# Orientation_bracelet.net
KiCad netlist of a schematic drawn in EAGLE
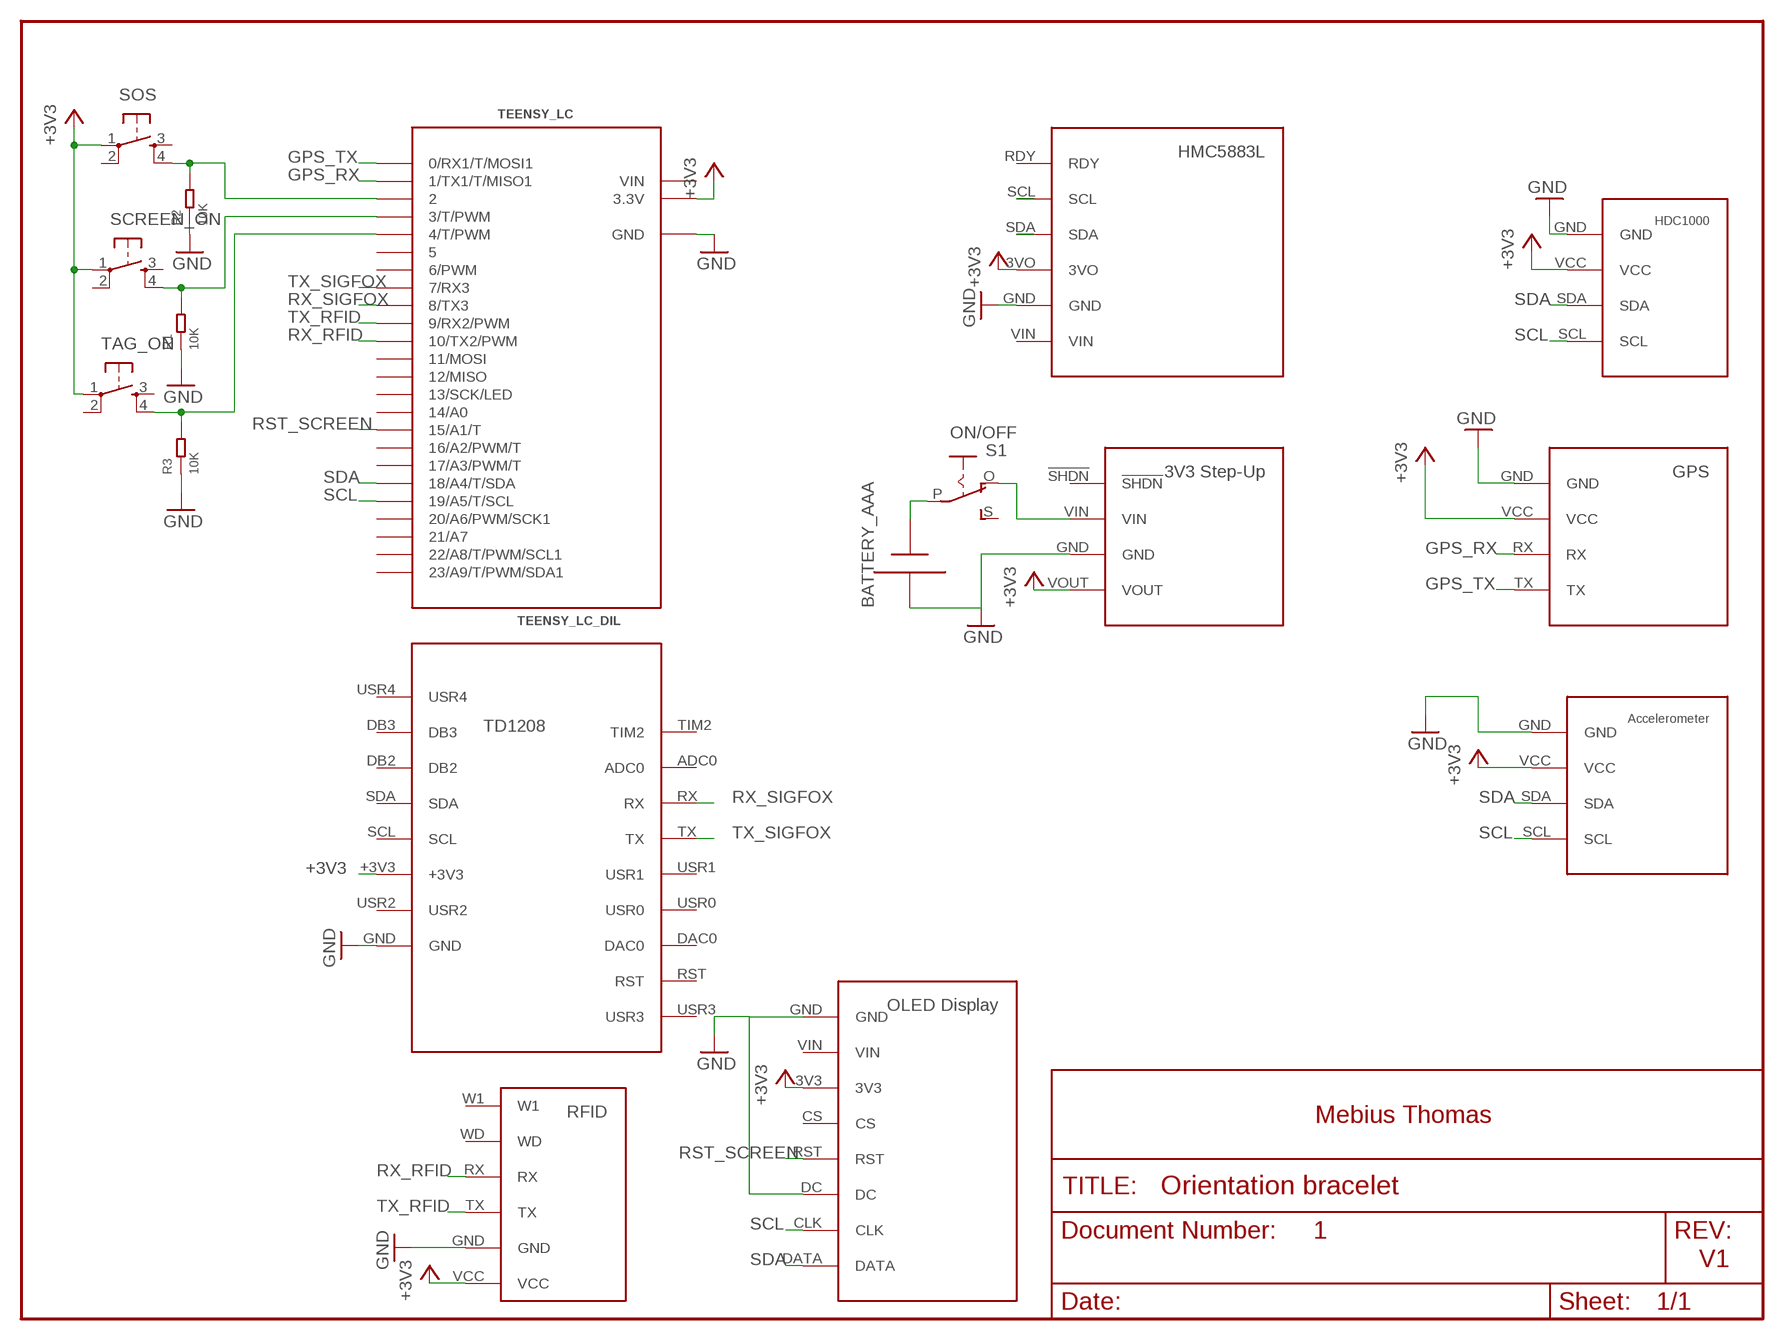
[diagram p0: schematic, sheet 1]

(export (version "E")
  (design (tool "Eeschema 10.0.6"))
  (components
    (comp (ref "BATTERY_AAA")
      (value "AAA")
      (footprint "eagle-import:12BH412")
      (libsource (lib "eagle-import") (part "AAA"))
    )
    (comp (ref "ON/OFF")
      (value "S1")
      (footprint "eagle-import:EG1218")
      (libsource (lib "eagle-import") (part "EG1218S"))
    )
    (comp (ref "R1")
      (value "10K")
      (footprint "eagle-import:PR-D2.3XL6.5MM")
      (fields (field (name "MPN") "FHCFR-1/4W-223J"))
      (libsource (lib "eagle-import") (part "DIP-RES-22K-5%-1/4W(PR-D2.3XL6.5MM)"))
    )
    (comp (ref "R2")
      (value "10K")
      (footprint "eagle-import:PR-D2.3XL6.5MM")
      (fields (field (name "MPN") "FHCFR-1/4W-223J"))
      (libsource (lib "eagle-import") (part "DIP-RES-22K-5%-1/4W(PR-D2.3XL6.5MM)"))
    )
    (comp (ref "R3")
      (value "10K")
      (footprint "eagle-import:PR-D2.3XL6.5MM")
      (fields (field (name "MPN") "FHCFR-1/4W-223J"))
      (libsource (lib "eagle-import") (part "DIP-RES-22K-5%-1/4W(PR-D2.3XL6.5MM)"))
    )
    (comp (ref "SCREEN_ON")
      (value "TAC_SWITCHPTH")
      (footprint "eagle-import:TACTILE-PTH")
      (libsource (lib "eagle-import") (part "TAC_SWITCHPTH"))
    )
    (comp (ref "SOS")
      (value "TAC_SWITCHPTH")
      (footprint "eagle-import:TACTILE-PTH")
      (libsource (lib "eagle-import") (part "TAC_SWITCHPTH"))
    )
    (comp (ref "TAG_ON")
      (value "TAC_SWITCHPTH")
      (footprint "eagle-import:TACTILE-PTH")
      (libsource (lib "eagle-import") (part "TAC_SWITCHPTH"))
    )
    (comp (ref "TEENSY_LC")
      (value "TEENSY_LC_DIL")
      (footprint "eagle-import:TEENSY_3.0-3.2&LC_DIL")
      (libsource (lib "eagle-import") (part "TEENSY_LC_DIL"))
    )
    (comp (ref "U$1")
      (value "OLED_DISPLAY")
      (footprint "eagle-import:OLED_DISPLAY")
      (libsource (lib "eagle-import") (part "OLED_DISPLAY"))
    )
    (comp (ref "U$2")
      (value "RFID\"")
      (footprint "eagle-import:RFID")
      (libsource (lib "eagle-import") (part "RFID{dblquote}"))
    )
    (comp (ref "U$3")
      (value "3V3_STEP-UP")
      (footprint "eagle-import:3V3_STEP-UP")
      (libsource (lib "eagle-import") (part "3V3_STEP-UP"))
    )
    (comp (ref "U$4")
      (value "ACCELEROMETER")
      (footprint "eagle-import:ACCELEROMETER")
      (libsource (lib "eagle-import") (part "ACCELEROMETER"))
    )
    (comp (ref "U$5")
      (value "HDC1000")
      (footprint "eagle-import:HDC1000")
      (libsource (lib "eagle-import") (part "HDC1000"))
    )
    (comp (ref "U$6")
      (value "GPS")
      (footprint "eagle-import:GPS")
      (libsource (lib "eagle-import") (part "GPS"))
    )
    (comp (ref "U$7")
      (value "HMC5883L")
      (footprint "eagle-import:HMC5883L")
      (libsource (lib "eagle-import") (part "HMC5883L"))
    )
    (comp (ref "U$8")
      (value "TD1208")
      (footprint "eagle-import:TD1208")
      (libsource (lib "eagle-import") (part "TD1208"))
    )
  )
  (nets
    (net (code "1") (name "+3V3") (class "Default")
      (node (ref "SCREEN_ON") (pin "1") (pinfunction "1_1") (pintype "passive"))
      (node (ref "SOS") (pin "1") (pinfunction "1_1") (pintype "passive"))
      (node (ref "TAG_ON") (pin "1") (pinfunction "1_1") (pintype "passive"))
      (node (ref "TEENSY_LC") (pin "3.3V") (pinfunction "3.3V_3.3V") (pintype "power_in"))
      (node (ref "U$1") (pin "3V3") (pinfunction "3V3_3V3") (pintype "bidirectional"))
      (node (ref "U$2") (pin "VCC") (pinfunction "VCC_VCC") (pintype "bidirectional"))
      (node (ref "U$3") (pin "VOUT") (pinfunction "VOUT_VOUT") (pintype "bidirectional"))
      (node (ref "U$4") (pin "VCC") (pinfunction "VCC_VCC") (pintype "bidirectional"))
      (node (ref "U$5") (pin "VCC") (pinfunction "VCC_VCC") (pintype "bidirectional"))
      (node (ref "U$6") (pin "VCC") (pinfunction "VCC_VCC") (pintype "bidirectional"))
      (node (ref "U$7") (pin "3VO") (pinfunction "3VO_3VO") (pintype "bidirectional"))
      (node (ref "U$8") (pin "+3V3") (pinfunction "+3V3_+3V3") (pintype "bidirectional"))
    )
    (net (code "2") (name "/GPS_RX") (class "Default")
      (node (ref "TEENSY_LC") (pin "1") (pinfunction "1/TX1/T/MISO1_1") (pintype "bidirectional"))
      (node (ref "U$6") (pin "RX") (pinfunction "RX_RX") (pintype "bidirectional"))
    )
    (net (code "3") (name "/GPS_TX") (class "Default")
      (node (ref "TEENSY_LC") (pin "0") (pinfunction "0/RX1/T/MOSI1_0") (pintype "bidirectional"))
      (node (ref "U$6") (pin "TX") (pinfunction "TX_TX") (pintype "bidirectional"))
    )
    (net (code "4") (name "/RST_SCREEN") (class "Default")
      (node (ref "TEENSY_LC") (pin "15/A1") (pinfunction "15/A1/T_15/A1") (pintype "bidirectional"))
      (node (ref "U$1") (pin "RST") (pinfunction "RST_RST") (pintype "bidirectional"))
    )
    (net (code "5") (name "/RX_RFID") (class "Default")
      (node (ref "TEENSY_LC") (pin "10") (pinfunction "10/TX2/PWM_10") (pintype "bidirectional"))
      (node (ref "U$2") (pin "RX") (pinfunction "RX_RX") (pintype "bidirectional"))
    )
    (net (code "6") (name "/RX_SIGFOX") (class "Default")
      (node (ref "TEENSY_LC") (pin "8") (pinfunction "8/TX3_8") (pintype "bidirectional"))
      (node (ref "U$8") (pin "RX") (pinfunction "RX_RX") (pintype "bidirectional"))
    )
    (net (code "7") (name "/SCL") (class "Default")
      (node (ref "TEENSY_LC") (pin "19/A5") (pinfunction "19/A5/T/SCL_19/A5") (pintype "bidirectional"))
      (node (ref "U$1") (pin "CLK") (pinfunction "CLK_CLK") (pintype "bidirectional"))
      (node (ref "U$4") (pin "SCL") (pinfunction "SCL_SCL") (pintype "bidirectional"))
      (node (ref "U$5") (pin "SCL") (pinfunction "SCL_SCL") (pintype "bidirectional"))
      (node (ref "U$7") (pin "SCL") (pinfunction "SCL_SCL") (pintype "bidirectional"))
    )
    (net (code "8") (name "/SDA") (class "Default")
      (node (ref "TEENSY_LC") (pin "18/A4") (pinfunction "18/A4/T/SDA_18/A4") (pintype "bidirectional"))
      (node (ref "U$1") (pin "DATA") (pinfunction "DATA_DATA") (pintype "bidirectional"))
      (node (ref "U$4") (pin "SDA") (pinfunction "SDA_SDA") (pintype "bidirectional"))
      (node (ref "U$5") (pin "SDA") (pinfunction "SDA_SDA") (pintype "bidirectional"))
      (node (ref "U$7") (pin "SDA") (pinfunction "SDA_SDA") (pintype "bidirectional"))
    )
    (net (code "9") (name "/TX_RFID") (class "Default")
      (node (ref "TEENSY_LC") (pin "9") (pinfunction "9/RX2/PWM_9") (pintype "bidirectional"))
      (node (ref "U$2") (pin "TX") (pinfunction "TX_TX") (pintype "bidirectional"))
    )
    (net (code "10") (name "/TX_SIGFOX") (class "Default")
      (node (ref "TEENSY_LC") (pin "7") (pinfunction "7/RX3_7") (pintype "bidirectional"))
      (node (ref "U$8") (pin "TX") (pinfunction "TX_TX") (pintype "bidirectional"))
    )
    (net (code "11") (name "/VIN") (class "Default")
      (node (ref "TEENSY_LC") (pin "VIN") (pinfunction "VIN_VIN") (pintype "power_in"))
    )
    (net (code "12") (name "GND") (class "Default")
      (node (ref "BATTERY_AAA") (pin "-") (pinfunction "-_-") (pintype "bidirectional"))
      (node (ref "R1") (pin "1") (pinfunction "1_1") (pintype "passive"))
      (node (ref "R2") (pin "1") (pinfunction "1_1") (pintype "passive"))
      (node (ref "R3") (pin "1") (pinfunction "1_1") (pintype "passive"))
      (node (ref "TEENSY_LC") (pin "AGND") (pinfunction "GND_AGND") (pintype "power_in"))
      (node (ref "TEENSY_LC") (pin "GND") (pinfunction "GND_GND") (pintype "power_in"))
      (node (ref "U$1") (pin "DC") (pinfunction "DC_DC") (pintype "bidirectional"))
      (node (ref "U$1") (pin "GND") (pinfunction "GND_GND") (pintype "bidirectional"))
      (node (ref "U$2") (pin "GND") (pinfunction "GND_GND") (pintype "bidirectional"))
      (node (ref "U$3") (pin "GND") (pinfunction "GND_GND") (pintype "bidirectional"))
      (node (ref "U$4") (pin "GND") (pinfunction "GND_GND") (pintype "bidirectional"))
      (node (ref "U$5") (pin "GND") (pinfunction "GND_GND") (pintype "bidirectional"))
      (node (ref "U$6") (pin "GND") (pinfunction "GND_GND") (pintype "bidirectional"))
      (node (ref "U$7") (pin "GND") (pinfunction "GND_GND") (pintype "bidirectional"))
      (node (ref "U$8") (pin "GND") (pinfunction "GND_GND") (pintype "bidirectional"))
    )
    (net (code "13") (name "Net-(BATTERY_AAA-Pad+)") (class "Default")
      (node (ref "BATTERY_AAA") (pin "+") (pinfunction "+_+") (pintype "bidirectional"))
      (node (ref "ON/OFF") (pin "P") (pinfunction "P_P") (pintype "passive"))
    )
    (net (code "14") (name "Net-(ON/OFF-PadO)") (class "Default")
      (node (ref "ON/OFF") (pin "O") (pinfunction "O_O") (pintype "passive"))
      (node (ref "U$3") (pin "VIN") (pinfunction "VIN_VIN") (pintype "bidirectional"))
    )
    (net (code "15") (name "Net-(R2-Pad2)") (class "Default")
      (node (ref "R2") (pin "2") (pinfunction "2_2") (pintype "passive"))
      (node (ref "SOS") (pin "4") (pinfunction "4_4") (pintype "passive"))
      (node (ref "TEENSY_LC") (pin "2") (pinfunction "2_2") (pintype "bidirectional"))
    )
    (net (code "16") (name "Net-(TEENSY_LC-3{slash}T{slash}PWM)") (class "Default")
      (node (ref "R1") (pin "2") (pinfunction "2_2") (pintype "passive"))
      (node (ref "SCREEN_ON") (pin "4") (pinfunction "4_4") (pintype "passive"))
      (node (ref "TEENSY_LC") (pin "3") (pinfunction "3/T/PWM_3") (pintype "bidirectional"))
    )
    (net (code "17") (name "Net-(TEENSY_LC-4{slash}T{slash}PWM)") (class "Default")
      (node (ref "R3") (pin "2") (pinfunction "2_2") (pintype "passive"))
      (node (ref "TAG_ON") (pin "4") (pinfunction "4_4") (pintype "passive"))
      (node (ref "TEENSY_LC") (pin "4") (pinfunction "4/T/PWM_4") (pintype "bidirectional"))
    )
    (net (code "18") (name "unconnected-(ON/OFF-PadS)") (class "Default")
      (node (ref "ON/OFF") (pin "S") (pinfunction "S_S") (pintype "passive"))
    )
    (net (code "19") (name "unconnected-(SCREEN_ON-Pad2)") (class "Default")
      (node (ref "SCREEN_ON") (pin "2") (pinfunction "2_2") (pintype "passive"))
    )
    (net (code "20") (name "unconnected-(SCREEN_ON-Pad3)") (class "Default")
      (node (ref "SCREEN_ON") (pin "3") (pinfunction "3_3") (pintype "passive"))
    )
    (net (code "21") (name "unconnected-(SOS-Pad2)") (class "Default")
      (node (ref "SOS") (pin "2") (pinfunction "2_2") (pintype "passive"))
    )
    (net (code "22") (name "unconnected-(SOS-Pad3)") (class "Default")
      (node (ref "SOS") (pin "3") (pinfunction "3_3") (pintype "passive"))
    )
    (net (code "23") (name "unconnected-(TAG_ON-Pad2)") (class "Default")
      (node (ref "TAG_ON") (pin "2") (pinfunction "2_2") (pintype "passive"))
    )
    (net (code "24") (name "unconnected-(TAG_ON-Pad3)") (class "Default")
      (node (ref "TAG_ON") (pin "3") (pinfunction "3_3") (pintype "passive"))
    )
    (net (code "25") (name "unconnected-(TEENSY_LC-6{slash}PWM-Pad6)") (class "Default")
      (node (ref "TEENSY_LC") (pin "6") (pinfunction "6/PWM_6") (pintype "bidirectional"))
    )
    (net (code "26") (name "unconnected-(TEENSY_LC-11{slash}MOSI-Pad11)") (class "Default")
      (node (ref "TEENSY_LC") (pin "11") (pinfunction "11/MOSI_11") (pintype "bidirectional"))
    )
    (net (code "27") (name "unconnected-(TEENSY_LC-12{slash}MISO-Pad12)") (class "Default")
      (node (ref "TEENSY_LC") (pin "12") (pinfunction "12/MISO_12") (pintype "bidirectional"))
    )
    (net (code "28") (name "unconnected-(TEENSY_LC-13{slash}SCK{slash}LED-Pad13)") (class "Default")
      (node (ref "TEENSY_LC") (pin "13") (pinfunction "13/SCK/LED_13") (pintype "bidirectional"))
    )
    (net (code "29") (name "unconnected-(TEENSY_LC-16{slash}A2{slash}PWM{slash}T-Pad16{slash}A2)") (class "Default")
      (node (ref "TEENSY_LC") (pin "16/A2") (pinfunction "16/A2/PWM/T_16/A2") (pintype "bidirectional"))
    )
    (net (code "30") (name "unconnected-(TEENSY_LC-17{slash}A3{slash}PWM{slash}T-Pad17{slash}A3)") (class "Default")
      (node (ref "TEENSY_LC") (pin "17/A3") (pinfunction "17/A3/PWM/T_17/A3") (pintype "bidirectional"))
    )
    (net (code "31") (name "unconnected-(TEENSY_LC-20{slash}A6{slash}PWM{slash}SCK1-Pad20{slash}A6)") (class "Default")
      (node (ref "TEENSY_LC") (pin "20/A6") (pinfunction "20/A6/PWM/SCK1_20/A6") (pintype "bidirectional"))
    )
    (net (code "32") (name "unconnected-(TEENSY_LC-22{slash}A8{slash}T{slash}PWM{slash}SCL1-Pad22{slash}A8)") (class "Default")
      (node (ref "TEENSY_LC") (pin "22/A8") (pinfunction "22/A8/T/PWM/SCL1_22/A8") (pintype "bidirectional"))
    )
    (net (code "33") (name "unconnected-(TEENSY_LC-23{slash}A9{slash}T{slash}PWM{slash}SDA1-Pad23{slash}A9)") (class "Default")
      (node (ref "TEENSY_LC") (pin "23/A9") (pinfunction "23/A9/T/PWM/SDA1_23/A9") (pintype "bidirectional"))
    )
    (net (code "34") (name "unconnected-(TEENSY_LC-Pad5)") (class "Default")
      (node (ref "TEENSY_LC") (pin "5") (pinfunction "5_5") (pintype "bidirectional"))
    )
    (net (code "35") (name "unconnected-(TEENSY_LC-Pad14{slash}A0)") (class "Default")
      (node (ref "TEENSY_LC") (pin "14/A0") (pinfunction "14/A0_14/A0") (pintype "bidirectional"))
    )
    (net (code "36") (name "unconnected-(TEENSY_LC-Pad21{slash}A7)") (class "Default")
      (node (ref "TEENSY_LC") (pin "21/A7") (pinfunction "21/A7_21/A7") (pintype "bidirectional"))
    )
    (net (code "37") (name "unconnected-(U$1-PadCS)") (class "Default")
      (node (ref "U$1") (pin "CS") (pinfunction "CS_CS") (pintype "bidirectional"))
    )
    (net (code "38") (name "unconnected-(U$1-PadVIN)") (class "Default")
      (node (ref "U$1") (pin "VIN") (pinfunction "VIN_VIN") (pintype "bidirectional"))
    )
    (net (code "39") (name "unconnected-(U$2-PadW1)") (class "Default")
      (node (ref "U$2") (pin "W1") (pinfunction "W1_W1") (pintype "bidirectional"))
    )
    (net (code "40") (name "unconnected-(U$2-PadWD)") (class "Default")
      (node (ref "U$2") (pin "WD") (pinfunction "WD_WD") (pintype "bidirectional"))
    )
    (net (code "41") (name "unconnected-(U$3-~{SHDN}-Pad!SHDN)") (class "Default")
      (node (ref "U$3") (pin "!SHDN") (pinfunction "~{SHDN}_!SHDN") (pintype "bidirectional"))
    )
    (net (code "42") (name "unconnected-(U$7-PadRDY)") (class "Default")
      (node (ref "U$7") (pin "RDY") (pinfunction "RDY_RDY") (pintype "bidirectional"))
    )
    (net (code "43") (name "unconnected-(U$7-PadVIN)") (class "Default")
      (node (ref "U$7") (pin "VIN") (pinfunction "VIN_VIN") (pintype "bidirectional"))
    )
    (net (code "44") (name "unconnected-(U$8-PadADC0)") (class "Default")
      (node (ref "U$8") (pin "ADC0") (pinfunction "ADC0_ADC0") (pintype "bidirectional"))
    )
    (net (code "45") (name "unconnected-(U$8-PadDAC0)") (class "Default")
      (node (ref "U$8") (pin "DAC0") (pinfunction "DAC0_DAC0") (pintype "bidirectional"))
    )
    (net (code "46") (name "unconnected-(U$8-PadDB2)") (class "Default")
      (node (ref "U$8") (pin "DB2") (pinfunction "DB2_DB2") (pintype "bidirectional"))
    )
    (net (code "47") (name "unconnected-(U$8-PadDB3)") (class "Default")
      (node (ref "U$8") (pin "DB3") (pinfunction "DB3_DB3") (pintype "bidirectional"))
    )
    (net (code "48") (name "unconnected-(U$8-PadRST)") (class "Default")
      (node (ref "U$8") (pin "RST") (pinfunction "RST_RST") (pintype "bidirectional"))
    )
    (net (code "49") (name "unconnected-(U$8-PadSCL)") (class "Default")
      (node (ref "U$8") (pin "SCL") (pinfunction "SCL_SCL") (pintype "bidirectional"))
    )
    (net (code "50") (name "unconnected-(U$8-PadSDA)") (class "Default")
      (node (ref "U$8") (pin "SDA") (pinfunction "SDA_SDA") (pintype "bidirectional"))
    )
    (net (code "51") (name "unconnected-(U$8-PadTIM2)") (class "Default")
      (node (ref "U$8") (pin "TIM2") (pinfunction "TIM2_TIM2") (pintype "bidirectional"))
    )
    (net (code "52") (name "unconnected-(U$8-PadUSR0)") (class "Default")
      (node (ref "U$8") (pin "USR0") (pinfunction "USR0_USR0") (pintype "bidirectional"))
    )
    (net (code "53") (name "unconnected-(U$8-PadUSR1)") (class "Default")
      (node (ref "U$8") (pin "USR1") (pinfunction "USR1_USR1") (pintype "bidirectional"))
    )
    (net (code "54") (name "unconnected-(U$8-PadUSR2)") (class "Default")
      (node (ref "U$8") (pin "USR2") (pinfunction "USR2_USR2") (pintype "bidirectional"))
    )
    (net (code "55") (name "unconnected-(U$8-PadUSR3)") (class "Default")
      (node (ref "U$8") (pin "USR3") (pinfunction "USR3_USR3") (pintype "bidirectional"))
    )
    (net (code "56") (name "unconnected-(U$8-PadUSR4)") (class "Default")
      (node (ref "U$8") (pin "USR4") (pinfunction "USR4_USR4") (pintype "bidirectional"))
    )
  )
)
